# Power.net
KiCad netlist of a schematic drawn in Altium Designer
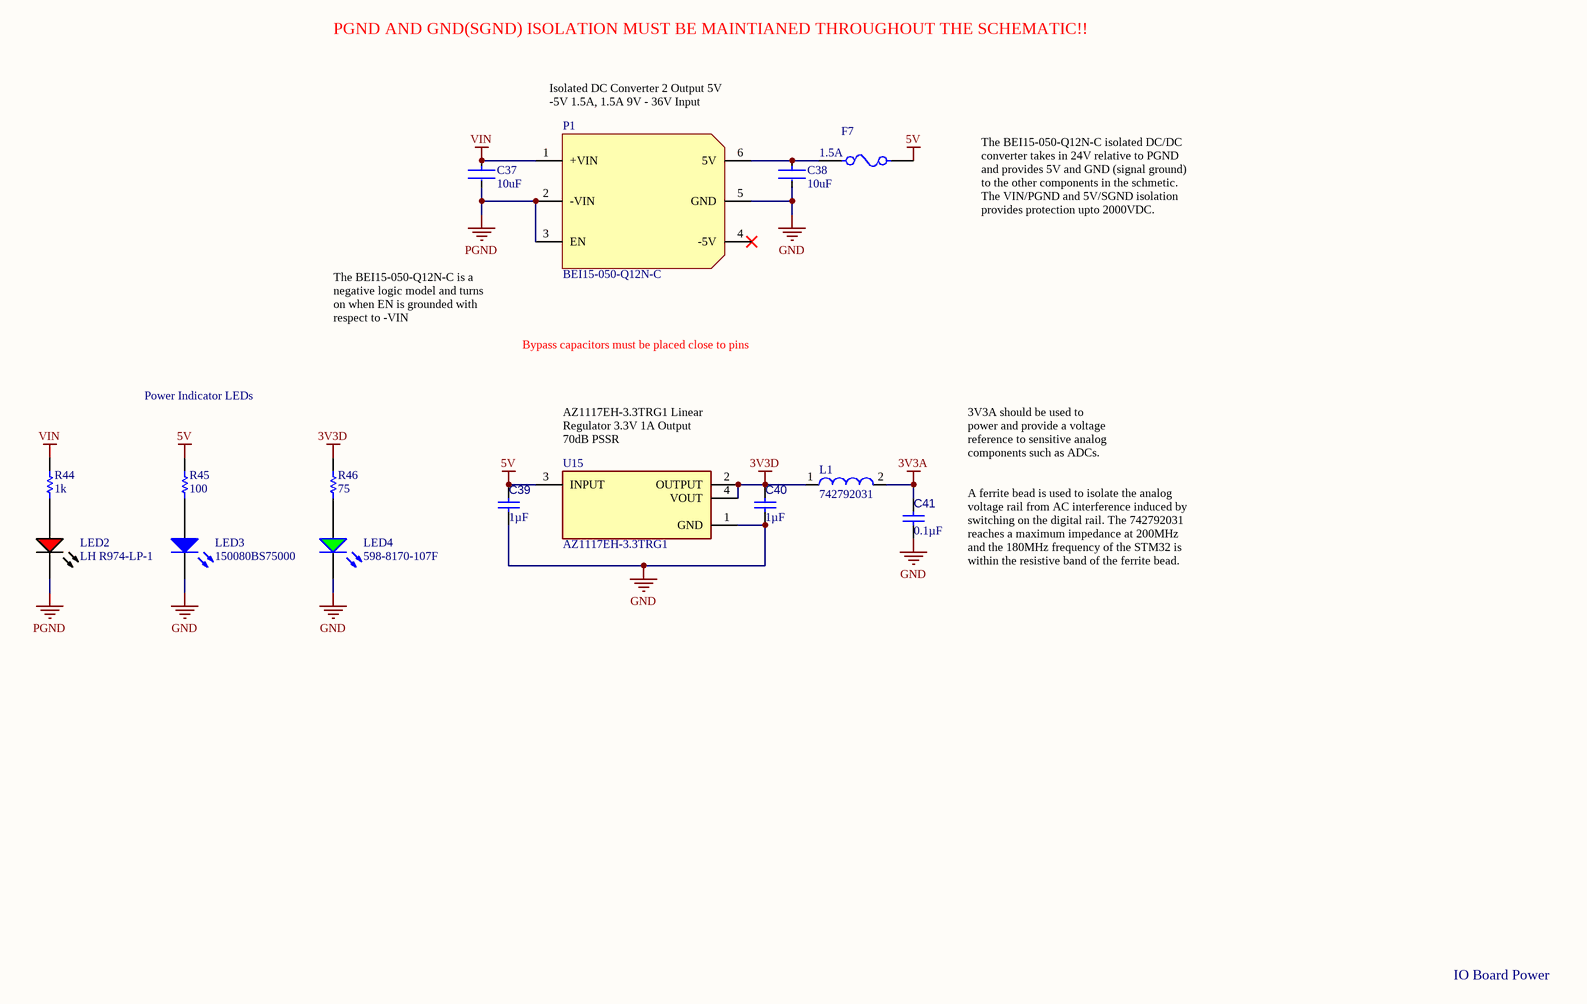
[diagram p0: Power.SchDoc]

(export (version "E")
  (design (tool "Eeschema 10.0.6"))
  (components
    (comp (ref "C37")
      (value "10uF")
      (footprint "FP-CL32-IPC_C")
      (description "Cap Ceramic 10uF 35V Y5V -20/+80% SMD 1210 +85°C Embossed T/R")
      (fields
        (field (name "MANUFACTURER") "Murata")
        (field (name "MANUFACTURER PART NUMBER") "GRM32ER71H106KA12L")
      )
      (libsource (lib "Altium Content Vault") (part "b4654b650e69147ec39a6b967a45e02"))
    )
    (comp (ref "C38")
      (value "10uF")
      (footprint "FP-CL32-IPC_C")
      (description "Cap Ceramic 10uF 35V Y5V -20/+80% SMD 1210 +85°C Embossed T/R")
      (fields
        (field (name "MANUFACTURER") "Murata")
        (field (name "MANUFACTURER PART NUMBER") "GRM32ER71H106KA12L")
      )
      (libsource (lib "Altium Content Vault") (part "b4654b650e69147ec39a6b967a45e02"))
    )
    (comp (ref "C39")
      (value "1µF")
      (footprint "CAPC2013X145X50ML20T25")
      (description "Chip Capacitor, 1 uF, +/-10%, 25 V, 0805 (2012 Metric)")
      (fields
        (field (name "MANUFACTURER") "KEMET")
        (field (name "MANUFACTURER PART NUMBER") "C0805C105K3RACTU")
      )
      (libsource (lib "Caltech FSAE") (part "CAP-NP-2"))
    )
    (comp (ref "C40")
      (value "1µF")
      (footprint "CAPC2013X145X50ML20T25")
      (description "Chip Capacitor, 1 uF, +/-10%, 25 V, 0805 (2012 Metric)")
      (fields
        (field (name "MANUFACTURER") "KEMET")
        (field (name "MANUFACTURER PART NUMBER") "C0805C105K3RACTU")
      )
      (libsource (lib "Caltech FSAE") (part "CAP-NP-2"))
    )
    (comp (ref "C41")
      (value "0.1µF")
      (footprint "CAPC2013X145X50ML20T25")
      (description "Chip Capacitor, 0.1 uF, +/-10%, 25 V, 0805 (2012 Metric)")
      (fields
        (field (name "MANUFACTURER") "KEMET")
        (field (name "MANUFACTURER PART NUMBER") "C0805C104K3RACTU")
      )
      (libsource (lib "Caltech FSAE") (part "CAP-NP-2"))
    )
    (comp (ref "F7")
      (value "1.5A")
      (footprint "FUSC1608X43N")
      (description "1.5A 0603 Fuse")
      (fields
        (field (name "MANUFACTURER_PART_NUMBER") "046701.5NR")
        (field (name "MOUSER PART NUMBER") "576-046701.5NR")
      )
      (libsource (lib "uControllerTemplate2021") (part "046701.5NR"))
    )
    (comp (ref "L1")
      (value "742792031")
      (footprint "SMD-0805")
      (description "SMD EMI Suppression Ferrite Bead WE-CBF, Z = 300 Ohm")
      (libsource (lib "Altium Content Vault") (part "PAS-IND-INDUCTOR-2"))
    )
    (comp (ref "LED2")
      (value "LH R974-LP-1")
      (footprint "0805_A")
      (description "LED RED DIFFUSED 0805 SMD")
      (libsource (lib "uControllerTemplate2021") (part "CMP-62016-000032-1"))
    )
    (comp (ref "LED3")
      (value "150080BS75000")
      (footprint "0805_A")
      (description "SMD mono-color Chip LED, WL-SMCW, Blue")
      (fields (field (name "MANUFACTURER") "Wuerth Elektronik"))
      (libsource (lib "Altium Content Vault") (part "WE-LED_K1A2-2"))
    )
    (comp (ref "LED4")
      (value "598-8170-107F")
      (footprint "0805_A")
      (description "Single Color, 2 V, -30 to 85 degC, 2-Pin SMD (0805), RoHS, Tape and Reel")
      (fields (field (name "MANUFACTURER") "Dialight"))
      (libsource (lib "uControllerTemplate2021") (part "CMP-2000-05655-1"))
    )
    (comp (ref "P1")
      (value "BEI15-050-Q12N-C")
      (footprint "BEI15-050-Q12N-C")
      (description "DC Converter 2 Output 5V -5V 1.5A, 1.5A 9V - 36V Input")
      (fields (field (name "MANUFACTURER") "Murata") (field (name "DIGI-KEY PART NUMBER") "811-2180-5-ND"))
      (libsource (lib "uControllerTemplate2021") (part "BEI15-050-Q12N-C"))
    )
    (comp (ref "R44")
      (value "1k")
      (footprint "RESC2013X50X35ML15T15")
      (description "Chip Resistor, 1k Ohm, +/- 1%, 125 mW, -55 to 155 degC, 0805 (2012 Metric)")
      (fields
        (field (name "MANUFACTURER") "Panasonic")
        (field (name "MANUFACTURER PART NUMBER") "ERA-6AEB102V")
      )
      (libsource (lib "Caltech FSAE") (part "RES-2"))
    )
    (comp (ref "R45")
      (value "100")
      (footprint "RESC2013X50X35ML15T15")
      (description "Chip Resistor, 100 Ohm, +/- 1%, 125 mW, -55 to 155 degC, 0805 (2012 Metric)")
      (fields
        (field (name "MANUFACTURER") "Panasonic")
        (field (name "MANUFACTURER PART NUMBER") "ERA-6AEB101V")
      )
      (libsource (lib "Caltech FSAE") (part "RES-2"))
    )
    (comp (ref "R46")
      (value "75")
      (footprint "RESC2013X50X35ML15T15")
      (description "Chip Resistor, 75 Ohm, +/- 1%, 125 mW, -55 to 155 degC, 0805 (2012 Metric)")
      (fields
        (field (name "MANUFACTURER") "Panasonic")
        (field (name "MANUFACTURER PART NUMBER") "ERA-6AEB750V")
      )
      (libsource (lib "Caltech FSAE") (part "RES-2"))
    )
    (comp (ref "U15")
      (value "AZ1117EH-3.3TRG1")
      (footprint "FP-SOT223-MFG")
      (description "IC REG LINEAR 3.3V 1A SOT223")
      (libsource (lib "Altium Content Vault") (part "d973f545ad55d44feb2bbb755596838"))
    )
  )
  (nets
    (net (code "1") (name "3V3A") (class "Default")
      (node (ref "C41") (pin "1") (pinfunction "1_1") (pintype "passive"))
      (node (ref "L1") (pin "2") (pinfunction "2_2") (pintype "passive"))
    )
    (net (code "2") (name "3V3D") (class "Default")
      (node (ref "C40") (pin "2") (pinfunction "2_2") (pintype "passive"))
      (node (ref "L1") (pin "1") (pinfunction "1_1") (pintype "passive"))
      (node (ref "R46") (pin "1") (pinfunction "1_1") (pintype "passive"))
      (node (ref "U15") (pin "2") (pinfunction "OUTPUT_2") (pintype "power_in"))
      (node (ref "U15") (pin "4") (pinfunction "VOUT_4") (pintype "power_in"))
    )
    (net (code "3") (name "5V") (class "Default")
      (node (ref "C39") (pin "2") (pinfunction "2_2") (pintype "passive"))
      (node (ref "F7") (pin "2") (pinfunction "2_2") (pintype "passive"))
      (node (ref "R45") (pin "2") (pinfunction "2_2") (pintype "passive"))
      (node (ref "U15") (pin "3") (pinfunction "INPUT_3") (pintype "power_in"))
    )
    (net (code "4") (name "GND") (class "Default")
      (node (ref "C38") (pin "2") (pinfunction "2_2") (pintype "passive"))
      (node (ref "C39") (pin "1") (pinfunction "1_1") (pintype "passive"))
      (node (ref "C40") (pin "1") (pinfunction "1_1") (pintype "passive"))
      (node (ref "C41") (pin "2") (pinfunction "2_2") (pintype "passive"))
      (node (ref "LED3") (pin "1") (pinfunction "K_1") (pintype "passive"))
      (node (ref "LED4") (pin "1") (pinfunction "K_1") (pintype "passive"))
      (node (ref "P1") (pin "5") (pinfunction "GND_5") (pintype "passive"))
      (node (ref "U15") (pin "1") (pinfunction "GND_1") (pintype "power_in"))
    )
    (net (code "5") (name "Net-(LED2-A)") (class "Default")
      (node (ref "LED2") (pin "2") (pinfunction "A_2") (pintype "passive"))
      (node (ref "R44") (pin "2") (pinfunction "2_2") (pintype "passive"))
    )
    (net (code "6") (name "Net-(LED3-A)") (class "Default")
      (node (ref "LED3") (pin "2") (pinfunction "A_2") (pintype "passive"))
      (node (ref "R45") (pin "1") (pinfunction "1_1") (pintype "passive"))
    )
    (net (code "7") (name "Net-(LED4-A)") (class "Default")
      (node (ref "LED4") (pin "2") (pinfunction "A_2") (pintype "passive"))
      (node (ref "R46") (pin "2") (pinfunction "2_2") (pintype "passive"))
    )
    (net (code "8") (name "Net-(P1-5V)") (class "Default")
      (node (ref "C38") (pin "1") (pinfunction "1_1") (pintype "passive"))
      (node (ref "F7") (pin "1") (pinfunction "1_1") (pintype "passive"))
      (node (ref "P1") (pin "6") (pinfunction "5V_6") (pintype "passive"))
    )
    (net (code "9") (name "PGND") (class "Default")
      (node (ref "C37") (pin "2") (pinfunction "2_2") (pintype "passive"))
      (node (ref "LED2") (pin "1") (pinfunction "K_1") (pintype "passive"))
      (node (ref "P1") (pin "2") (pinfunction "-VIN_2") (pintype "passive"))
      (node (ref "P1") (pin "3") (pinfunction "EN_3") (pintype "passive"))
    )
    (net (code "10") (name "VIN") (class "Default")
      (node (ref "C37") (pin "1") (pinfunction "1_1") (pintype "passive"))
      (node (ref "P1") (pin "1") (pinfunction "+VIN_1") (pintype "passive"))
      (node (ref "R44") (pin "1") (pinfunction "1_1") (pintype "passive"))
    )
    (net (code "11") (name "unconnected-(P1--5V-Pad4)") (class "Default")
      (node (ref "P1") (pin "4") (pinfunction "-5V_4") (pintype "passive+no_connect"))
    )
  )
)
